# MacSet-L-V2_0_0_2.net
KiCad netlist of a schematic drawn in Altium Designer
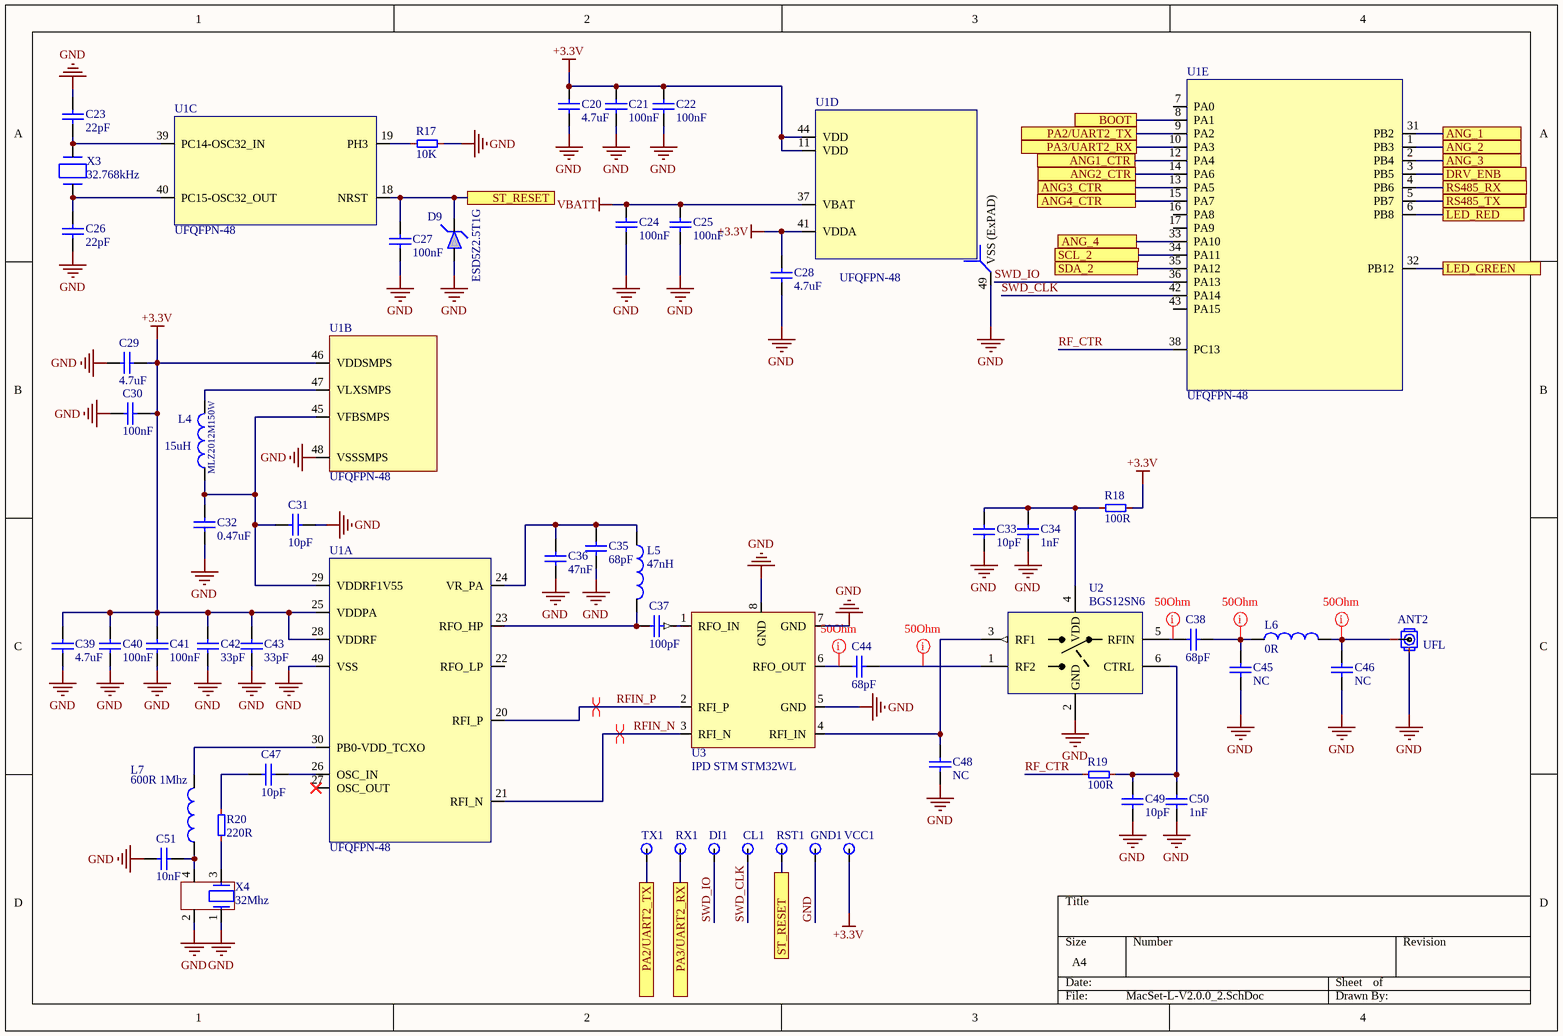
[diagram p0: MacSet-L-V2.0.0_2.SchDoc]

(export (version "E")
  (design (tool "Eeschema 10.0.6"))
  (components
    (comp (ref "ANT2")
      (value "UFL")
      (footprint "UFL")
      (description "SMA Connector")
      (libsource (lib "macnman_3.0") (part "SMA Antenna"))
    )
    (comp (ref "C20")
      (value "4.7uF")
      (footprint "CAP0603")
      (description "MLCC - SMD/SMT 4.7 uF 16 VDC 10% 0603 X5R")
      (fields
        (field (name "MANUFACTURER_PART_NUMBER") "CL10A475KQ8NNNC")
        (field (name "MANUFACTURER") "Samsung Electro-Mechanics")
      )
      (libsource (lib "macnman_2.0") (part "Capa_0603"))
    )
    (comp (ref "C21")
      (value "100nF")
      (footprint "CAP0402")
      (description "Ceramic Capacitor X7R 0402 100nF 16V")
      (fields
        (field (name "MANUFACTURER_PART_NUMBER") "GRM155R71C104JA88D")
        (field (name "MANUFACTURER") "MURATA")
      )
      (libsource (lib "macnman_2.0") (part "Capa_0402"))
    )
    (comp (ref "C22")
      (value "100nF")
      (footprint "CAP0402")
      (description "Ceramic Capacitor X7R 0402 100nF 16V")
      (fields
        (field (name "MANUFACTURER_PART_NUMBER") "GRM155R71C104JA88D")
        (field (name "MANUFACTURER") "MURATA")
      )
      (libsource (lib "macnman_2.0") (part "Capa_0402"))
    )
    (comp (ref "C23")
      (value "22pF")
      (footprint "CAP0402")
      (description "Multilayer Ceramic Capacitors MLCC - SMD/SMT 50 V 22pF C0G 0402 5%")
      (fields
        (field (name "MANUFACTURER_PART_NUMBER") "GCM1555C1H220JA16D")
        (field (name "MANUFACTURER") "Murata")
      )
      (libsource (lib "macnman_2.0") (part "Capa_0402"))
    )
    (comp (ref "C24")
      (value "100nF")
      (footprint "CAP0402")
      (description "Ceramic Capacitor X7R 0402 100nF 16V")
      (fields
        (field (name "MANUFACTURER_PART_NUMBER") "GRM155R71C104JA88D")
        (field (name "MANUFACTURER") "MURATA")
      )
      (libsource (lib "macnman_2.0") (part "Capa_0402"))
    )
    (comp (ref "C25")
      (value "100nF")
      (footprint "CAP0402")
      (description "Ceramic Capacitor X7R 0402 100nF 16V")
      (fields
        (field (name "MANUFACTURER_PART_NUMBER") "GRM155R71C104JA88D")
        (field (name "MANUFACTURER") "MURATA")
      )
      (libsource (lib "macnman_2.0") (part "Capa_0402"))
    )
    (comp (ref "C26")
      (value "22pF")
      (footprint "CAP0402")
      (description "Multilayer Ceramic Capacitors MLCC - SMD/SMT 50 V 22pF C0G 0402 5%")
      (fields
        (field (name "MANUFACTURER_PART_NUMBER") "GCM1555C1H220JA16D")
        (field (name "MANUFACTURER") "Murata")
      )
      (libsource (lib "macnman_2.0") (part "Capa_0402"))
    )
    (comp (ref "C27")
      (value "100nF")
      (footprint "CAP0402")
      (description "Ceramic Capacitor X7R 0402 100nF 16V")
      (fields
        (field (name "MANUFACTURER_PART_NUMBER") "GRM155R71C104JA88D")
        (field (name "MANUFACTURER") "MURATA")
      )
      (libsource (lib "macnman_2.0") (part "Capa_0402"))
    )
    (comp (ref "C28")
      (value "4.7uF")
      (footprint "CAP0603")
      (description "MLCC - SMD/SMT 4.7 uF 16 VDC 10% 0603 X5R")
      (fields
        (field (name "MANUFACTURER_PART_NUMBER") "CL10A475KQ8NNNC")
        (field (name "MANUFACTURER") "Samsung Electro-Mechanics")
      )
      (libsource (lib "macnman_2.0") (part "Capa_0603"))
    )
    (comp (ref "C29")
      (value "4.7uF")
      (footprint "CAP0603")
      (description "MLCC - SMD/SMT 4.7 uF 16 VDC 10% 0603 X5R")
      (fields
        (field (name "MANUFACTURER_PART_NUMBER") "CL10A475KQ8NNNC")
        (field (name "MANUFACTURER") "Samsung Electro-Mechanics")
      )
      (libsource (lib "macnman_2.0") (part "Capa_0603"))
    )
    (comp (ref "C30")
      (value "100nF")
      (footprint "CAP0402")
      (description "Ceramic Capacitor X7R 0402 100nF 16V")
      (fields
        (field (name "MANUFACTURER_PART_NUMBER") "GRM155R71C104JA88D")
        (field (name "MANUFACTURER") "MURATA")
      )
      (libsource (lib "macnman_2.0") (part "Capa_0402"))
    )
    (comp (ref "C31")
      (value "10pF")
      (footprint "CAP0402")
      (description "Multilayer Ceramic Capacitors MLCC - SMD/SMT 50 V 10pF C0G 0402 10%")
      (fields
        (field (name "MANUFACTURER_PART_NUMBER") "CC0402JRNPO9BN100")
        (field (name "MANUFACTURER") "YAGEO")
      )
      (libsource (lib "macnman_2.0") (part "Capa_0402"))
    )
    (comp (ref "C32")
      (value "0.47uF")
      (footprint "CAP0603")
      (description "MLCC - SMD/SMT 0.47 uF 16 VDC 10% 0603 X5R")
      (fields
        (field (name "MANUFACTURER_PART_NUMBER") "CC0603KRX7R0BB474")
        (field (name "MANUFACTURER") "Yageo")
      )
      (libsource (lib "macnman_2.0") (part "Capa_0603"))
    )
    (comp (ref "C33")
      (value "10pF")
      (footprint "CAP0402")
      (description "Multilayer Ceramic Capacitors MLCC - SMD/SMT 50 V 10pF C0G 0402 10%")
      (fields
        (field (name "MANUFACTURER_PART_NUMBER") "CC0402JRNPO9BN100")
        (field (name "MANUFACTURER") "YAGEO")
      )
      (libsource (lib "macnman_2.0") (part "Capa_0402"))
    )
    (comp (ref "C34")
      (value "1nF")
      (footprint "CAP0402")
      (description "Multilayer Ceramic Capacitors MLCC - SMD/SMT 50 V 1nF C0G 0402 10%")
      (fields
        (field (name "MANUFACTURER_PART_NUMBER") "CC0402KRX7R9BB102")
        (field (name "MANUFACTURER") "YAGEO")
      )
      (libsource (lib "macnman_2.0") (part "Capa_0402"))
    )
    (comp (ref "C35")
      (value "68pF")
      (footprint "CAP0402")
      (description "Multilayer Ceramic Capacitors MLCC - SMD/SMT 50 V 68pF C0G 0402 5%")
      (fields
        (field (name "MANUFACTURER_PART_NUMBER") "CC0402JRNPO9BN680")
        (field (name "MANUFACTURER") "YAGEO")
      )
      (libsource (lib "macnman_2.0") (part "Capa_0402"))
    )
    (comp (ref "C36")
      (value "47nF")
      (footprint "CAP0402")
      (description "Multilayer Ceramic Capacitors MLCC - SMD/SMT 50 V 47nF C0G 0402 10%")
      (fields
        (field (name "MANUFACTURER_PART_NUMBER") "0402B473K500CT")
        (field (name "MANUFACTURER") "Walsin")
      )
      (libsource (lib "macnman_2.0") (part "Capa_0402"))
    )
    (comp (ref "C37")
      (value "100pF")
      (footprint "CAP0402")
      (description "Multilayer Ceramic Capacitors MLCC - SMD/SMT 50 V 100pF C0G 0402 10%")
      (fields
        (field (name "MANUFACTURER_PART_NUMBER") "CC0402KRNPO9BN101")
        (field (name "MANUFACTURER") "YAGEO")
      )
      (libsource (lib "") (part "Capa_0402_1"))
    )
    (comp (ref "C38")
      (value "68pF")
      (footprint "CAP0402")
      (description "Multilayer Ceramic Capacitors MLCC - SMD/SMT 50 V 68pF C0G 0402 5%")
      (fields
        (field (name "MANUFACTURER_PART_NUMBER") "CC0402JRNPO9BN680")
        (field (name "MANUFACTURER") "YAGEO")
      )
      (libsource (lib "macnman_2.0") (part "Capa_0402"))
    )
    (comp (ref "C39")
      (value "4.7uF")
      (footprint "CAP0603")
      (description "MLCC - SMD/SMT 4.7 uF 16 VDC 10% 0603 X5R")
      (fields
        (field (name "MANUFACTURER_PART_NUMBER") "CL10A475KQ8NNNC")
        (field (name "MANUFACTURER") "Samsung Electro-Mechanics")
      )
      (libsource (lib "macnman_2.0") (part "Capa_0603"))
    )
    (comp (ref "C40")
      (value "100nF")
      (footprint "CAP0402")
      (description "Ceramic Capacitor X7R 0402 100nF 16V")
      (fields
        (field (name "MANUFACTURER_PART_NUMBER") "GRM155R71C104JA88D")
        (field (name "MANUFACTURER") "MURATA")
      )
      (libsource (lib "macnman_2.0") (part "Capa_0402"))
    )
    (comp (ref "C41")
      (value "100nF")
      (footprint "CAP0402")
      (description "Ceramic Capacitor X7R 0402 100nF 16V")
      (fields
        (field (name "MANUFACTURER_PART_NUMBER") "GRM155R71C104JA88D")
        (field (name "MANUFACTURER") "MURATA")
      )
      (libsource (lib "macnman_2.0") (part "Capa_0402"))
    )
    (comp (ref "C42")
      (value "33pF")
      (footprint "CAP0402")
      (description "Ceramic Capacitor C0G, NP0 0402 33pF 35V")
      (fields
        (field (name "MANUFACTURER_PART_NUMBER") "CC0402JRNPO9BN330")
        (field (name "MANUFACTURER") "MURATA")
      )
      (libsource (lib "macnman_2.0") (part "Capa_0402"))
    )
    (comp (ref "C43")
      (value "33pF")
      (footprint "CAP0402")
      (description "Ceramic Capacitor C0G, NP0 0402 33pF 35V")
      (fields
        (field (name "MANUFACTURER_PART_NUMBER") "CC0402JRNPO9BN330")
        (field (name "MANUFACTURER") "MURATA")
      )
      (libsource (lib "macnman_2.0") (part "Capa_0402"))
    )
    (comp (ref "C44")
      (value "68pF")
      (footprint "CAP0402")
      (description "Multilayer Ceramic Capacitors MLCC - SMD/SMT 50 V 68pF C0G 0402 5%")
      (fields
        (field (name "MANUFACTURER_PART_NUMBER") "CC0402JRNPO9BN680")
        (field (name "MANUFACTURER") "YAGEO")
      )
      (libsource (lib "macnman_2.0") (part "Capa_0402"))
    )
    (comp (ref "C45")
      (value "NC")
      (footprint "CAP0402")
      (description "Multilayer Ceramic Capacitors MLCC - SMD/SMT 50 V 2.4pF C0G 0402 10%")
      (fields
        (field (name "MANUFACTURER_PART_NUMBER") "CC0402CRNPO9BN2R4")
        (field (name "MANUFACTURER") "YAGEO")
      )
      (libsource (lib "macnman_2.0") (part "Capa_0402"))
    )
    (comp (ref "C46")
      (value "NC")
      (footprint "CAP0402")
      (description "Multilayer Ceramic Capacitors MLCC - SMD/SMT 50 V 2.4pF C0G 0402 10%")
      (fields
        (field (name "MANUFACTURER_PART_NUMBER") "CC0402CRNPO9BN2R4")
        (field (name "MANUFACTURER") "YAGEO")
      )
      (libsource (lib "macnman_2.0") (part "Capa_0402"))
    )
    (comp (ref "C47")
      (value "10pF")
      (footprint "CAP0402")
      (description "Multilayer Ceramic Capacitors MLCC - SMD/SMT 50 V 10pF C0G 0402 10%")
      (fields
        (field (name "MANUFACTURER_PART_NUMBER") "CC0402JRNPO9BN100")
        (field (name "MANUFACTURER") "YAGEO")
      )
      (libsource (lib "macnman_2.0") (part "Capa_0402"))
    )
    (comp (ref "C48") (value "NC") (footprint "CAP0402") (libsource (lib "macnman_2.0") (part "Capa_0402")))
    (comp (ref "C49")
      (value "10pF")
      (footprint "CAP0402")
      (description "Multilayer Ceramic Capacitors MLCC - SMD/SMT 50 V 10pF C0G 0402 10%")
      (fields
        (field (name "MANUFACTURER_PART_NUMBER") "CC0402JRNPO9BN100")
        (field (name "MANUFACTURER") "YAGEO")
      )
      (libsource (lib "macnman_2.0") (part "Capa_0402"))
    )
    (comp (ref "C50")
      (value "1nF")
      (footprint "CAP0402")
      (description "Multilayer Ceramic Capacitors MLCC - SMD/SMT 50 V 1nF C0G 0402 10%")
      (fields
        (field (name "MANUFACTURER_PART_NUMBER") "CC0402KRX7R9BB102")
        (field (name "MANUFACTURER") "YAGEO")
      )
      (libsource (lib "macnman_2.0") (part "Capa_0402"))
    )
    (comp (ref "C51")
      (value "10nF")
      (footprint "CAP0402")
      (description "Multilayer Ceramic Capacitors MLCC - SMD/SMT 50 V 10nF C0G 0402 10%")
      (fields
        (field (name "MANUFACTURER_PART_NUMBER") "CC0402KRX7R9BB103")
        (field (name "MANUFACTURER") "YAGEO")
      )
      (libsource (lib "macnman_2.0") (part "Capa_0402"))
    )
    (comp (ref "CL1")
      (value "-")
      (footprint "TH_Pad")
      (description "Through Hole pad 1mm 0.5mm Hole")
      (libsource (lib "macnman_2.0") (part "TH_PAD"))
    )
    (comp (ref "D9")
      (value "ESD5Z2.5T1G")
      (footprint "SOD523")
      (description "ESD Protection Diodes / TVS Diodes 2.5V ESD Protection Unidirectional")
      (fields (field (name "MANUFACTURER") "onsemi"))
      (libsource (lib "macnman_2.0") (part "DIODE-ESD"))
    )
    (comp (ref "DI1")
      (value "-")
      (footprint "TH_Pad")
      (description "Through Hole pad 1mm 0.5mm Hole")
      (libsource (lib "macnman_2.0") (part "TH_PAD"))
    )
    (comp (ref "GND1")
      (value "-")
      (footprint "TH_Pad")
      (description "Through Hole pad 1mm 0.5mm Hole")
      (libsource (lib "macnman_2.0") (part "TH_PAD"))
    )
    (comp (ref "L4")
      (value "15uH")
      (footprint "IND_2012")
      (description "MLZ2012 Multilayer Shielded Inductor 15µH, ±5%")
      (fields (field (name "MANUFACTURER_PART_NUMBER") "MLZ2012M150W") (field (name "MANUFACTURER") "TDK"))
      (libsource (lib "MB1849") (part "Inductor"))
    )
    (comp (ref "L5")
      (value "47nH")
      (footprint "IND_0402")
      (description "47nH High frequency chip inductor ±5%  0402")
      (fields
        (field (name "MANUFACTURER_PART_NUMBER") "LQG15HN47NJ02D")
        (field (name "MANUFACTURER") "Murata")
      )
      (libsource (lib "macnman_2.0") (part "Inductor"))
    )
    (comp (ref "L6")
      (value "0R")
      (footprint "IND_0402")
      (description "Thick Film Resistors - SMD 1/16watt 0R 1% 0402 Commercial Use")
      (fields
        (field (name "MANUFACTURER_PART_NUMBER") "RC0402FR-070RL")
        (field (name "MANUFACTURER") "YAGIO")
      )
      (libsource (lib "macnman_2.0") (part "Inductor"))
    )
    (comp (ref "L7")
      (value "600R 1Mhz")
      (footprint "IND_0402")
      (description "47nH High frequency chip inductor ±5%  0402")
      (fields (field (name "MANUFACTURER_PART_NUMBER") "GZ1005D601TF") (field (name "MANUFACTURER") "Murata"))
      (libsource (lib "macnman_2.0") (part "Inductor"))
    )
    (comp (ref "R17")
      (value "10K")
      (footprint "RESC0402")
      (description "Thick Film Resistors - SMD 1/16watt 10Kohms 0402 1% Commercial Use")
      (fields
        (field (name "MANUFACTURER_PART_NUMBER") "CRCW040210K0FKEDC")
        (field (name "MANUFACTURER") "Vishay")
      )
      (libsource (lib "macnman_2.0") (part "RES_0402"))
    )
    (comp (ref "R18")
      (value "100R")
      (footprint "RESC0402")
      (description "Thin Film Resistors 100 OHM 1% 50PPM 1/1 6W 0402")
      (fields
        (field (name "MANUFACTURER_PART_NUMBER") "RC0402FR-07100RL")
        (field (name "MANUFACTURER") "YAGEO")
      )
      (libsource (lib "macnman_2.0") (part "RES_0402"))
    )
    (comp (ref "R19")
      (value "100R")
      (footprint "RESC0402")
      (description "Thin Film Resistors 100 OHM 1% 50PPM 1/1 6W 0402")
      (fields
        (field (name "MANUFACTURER_PART_NUMBER") "RC0402FR-07100RL")
        (field (name "MANUFACTURER") "YAGEO")
      )
      (libsource (lib "macnman_2.0") (part "RES_0402"))
    )
    (comp (ref "R20")
      (value "220R")
      (footprint "RESC0402")
      (description "Thin Film Resistors 220 OHM 1% 50PPM 1/1 6W 0402")
      (fields
        (field (name "MANUFACTURER_PART_NUMBER") "0402WGF2200TCE")
        (field (name "MANUFACTURER") "Royalohm")
      )
      (libsource (lib "macnman_2.0") (part "RES_0402"))
    )
    (comp (ref "RST1")
      (value "-")
      (footprint "TH_Pad")
      (description "Through Hole pad 1mm 0.5mm Hole")
      (libsource (lib "macnman_2.0") (part "TH_PAD"))
    )
    (comp (ref "RX1")
      (value "-")
      (footprint "TH_Pad")
      (description "Through Hole pad 1mm 0.5mm Hole")
      (libsource (lib "macnman_2.0") (part "TH_PAD"))
    )
    (comp (ref "TX1")
      (value "-")
      (footprint "TH_Pad")
      (description "Through Hole pad 1mm 0.5mm Hole")
      (libsource (lib "macnman_2.0") (part "TH_PAD"))
    )
    (comp (ref "U1")
      (value "UFQFPN-48")
      (footprint "STM32WLxx_QFN48")
      (fields
        (field (name "MANUFACTURER") "STMicroelectronics")
        (field (name "MANUFACTURER_PART_NUMBER") "STM32WL5CCU6")
      )
      (libsource (lib "macnman_3.0") (part "STM32WLE5C8U6_O"))
    )
    (comp (ref "U2")
      (value "BGS12SN6")
      (footprint "SON40P70X40-6N")
      (description "DC switch - Ultra-Low  SPDT analog switch")
      (fields (field (name "MANUFACTURER") "INFINEON"))
      (libsource (lib "macnman_2.0") (part "BGS12SN6"))
    )
    (comp (ref "U3")
      (value "IPD STM STM32WL")
      (footprint "IPD STM")
      (fields
        (field (name "MANUFACTURER") "STMICROELECTRONICS")
        (field (name "MANUFACTURER_PART_NUMBER") "MLPF-WL-02D3")
      )
      (libsource (lib "macnman_3.0") (part "IPD ST STM32WL"))
    )
    (comp (ref "VCC1")
      (value "-")
      (footprint "TH_Pad")
      (description "Through Hole pad 1mm 0.5mm Hole")
      (libsource (lib "macnman_2.0") (part "TH_PAD"))
    )
    (comp (ref "X3")
      (value "32.768kHz")
      (footprint "OSC_3215")
      (description "Crystal Osc 3215 32.768kHz 12pF")
      (fields
        (field (name "MANUFACTURER_PART_NUMBER") "ECS-.327-12.5-34B-TR")
        (field (name "MANUFACTURER") "ECS")
      )
      (libsource (lib "macnman_2.0") (part "OSC_2012"))
    )
    (comp (ref "X4")
      (value "32Mhz")
      (footprint "OSC_2016")
      (description "TCXO Oscillators TG2016SMN 32.0000M-MCGNNM0: TCXO 2.8V 3.3V 0.5PPM -40 85C NON O/E 1K TR")
      (fields
        (field (name "MANUFACTURER_PART_NUMBER") "TG2016SMN 32.0000M-MCGNNM0")
        (field (name "MANUFACTURER") "Epson")
      )
      (libsource (lib "macnman_2.0") (part "OSC_2016"))
    )
  )
  (nets
    (net (code "1") (name "+3.3V") (class "Default")
      (node (ref "C20") (pin "2") (pinfunction "2_2") (pintype "passive"))
      (node (ref "C21") (pin "1") (pinfunction "1_1") (pintype "passive"))
      (node (ref "C22") (pin "1") (pinfunction "1_1") (pintype "passive"))
      (node (ref "C28") (pin "2") (pinfunction "2_2") (pintype "passive"))
      (node (ref "C29") (pin "2") (pinfunction "2_2") (pintype "passive"))
      (node (ref "C30") (pin "1") (pinfunction "1_1") (pintype "passive"))
      (node (ref "C39") (pin "2") (pinfunction "2_2") (pintype "passive"))
      (node (ref "C40") (pin "1") (pinfunction "1_1") (pintype "passive"))
      (node (ref "C41") (pin "1") (pinfunction "1_1") (pintype "passive"))
      (node (ref "C42") (pin "1") (pinfunction "1_1") (pintype "passive"))
      (node (ref "C43") (pin "1") (pinfunction "1_1") (pintype "passive"))
      (node (ref "R18") (pin "1") (pinfunction "1_1") (pintype "passive"))
      (node (ref "U1") (pin "11") (pinfunction "VDD_11") (pintype "passive"))
      (node (ref "U1") (pin "25") (pinfunction "VDDPA_25") (pintype "passive"))
      (node (ref "U1") (pin "28") (pinfunction "VDDRF_28") (pintype "passive"))
      (node (ref "U1") (pin "41") (pinfunction "VDDA_41") (pintype "passive"))
      (node (ref "U1") (pin "44") (pinfunction "VDD_44") (pintype "passive"))
      (node (ref "U1") (pin "46") (pinfunction "VDDSMPS_46") (pintype "passive"))
      (node (ref "VCC1") (pin "1") (pinfunction "RX_1") (pintype "passive"))
    )
    (net (code "2") (name "/ANG1_CTR") (class "Default")
      (node (ref "U1") (pin "12") (pinfunction "PA4_12") (pintype "passive"))
    )
    (net (code "3") (name "/ANG2_CTR") (class "Default")
      (node (ref "U1") (pin "14") (pinfunction "PA6_14") (pintype "passive"))
    )
    (net (code "4") (name "/ANG3_CTR") (class "Default")
      (node (ref "U1") (pin "13") (pinfunction "PA5_13") (pintype "passive"))
    )
    (net (code "5") (name "/ANG4_CTR") (class "Default")
      (node (ref "U1") (pin "15") (pinfunction "PA7_15") (pintype "passive"))
    )
    (net (code "6") (name "/ANG_1") (class "Default")
      (node (ref "U1") (pin "31") (pinfunction "PB2_31") (pintype "passive"))
    )
    (net (code "7") (name "/ANG_2") (class "Default")
      (node (ref "U1") (pin "1") (pinfunction "PB3_1") (pintype "passive"))
    )
    (net (code "8") (name "/ANG_3") (class "Default")
      (node (ref "U1") (pin "2") (pinfunction "PB4_2") (pintype "passive"))
    )
    (net (code "9") (name "/ANG_4") (class "Default")
      (node (ref "U1") (pin "33") (pinfunction "PA10_33") (pintype "passive"))
    )
    (net (code "10") (name "/BOOT") (class "Default")
      (node (ref "U1") (pin "8") (pinfunction "PA1_8") (pintype "passive"))
    )
    (net (code "11") (name "/DRV_ENB") (class "Default")
      (node (ref "U1") (pin "3") (pinfunction "PB5_3") (pintype "passive"))
    )
    (net (code "12") (name "/LED_GREEN") (class "Default")
      (node (ref "U1") (pin "32") (pinfunction "PB12_32") (pintype "passive"))
    )
    (net (code "13") (name "/LED_RED") (class "Default")
      (node (ref "U1") (pin "6") (pinfunction "PB8_6") (pintype "passive"))
    )
    (net (code "14") (name "/PA2{slash}UART2_TX") (class "Default")
      (node (ref "TX1") (pin "1") (pinfunction "RX_1") (pintype "passive"))
      (node (ref "U1") (pin "9") (pinfunction "PA2_9") (pintype "passive"))
    )
    (net (code "15") (name "/PA3{slash}UART2_RX") (class "Default")
      (node (ref "RX1") (pin "1") (pinfunction "RX_1") (pintype "passive"))
      (node (ref "U1") (pin "10") (pinfunction "PA3_10") (pintype "passive"))
    )
    (net (code "16") (name "/RFIN_N") (class "Default")
      (node (ref "U1") (pin "21") (pinfunction "RFI_N_21") (pintype "passive"))
      (node (ref "U3") (pin "3") (pinfunction "RFI_N_3") (pintype "output"))
    )
    (net (code "17") (name "/RFIN_P") (class "Default")
      (node (ref "U1") (pin "20") (pinfunction "RFI_P_20") (pintype "passive"))
      (node (ref "U3") (pin "2") (pinfunction "RFI_P_2") (pintype "output"))
    )
    (net (code "18") (name "/RF_CTR") (class "Default")
      (node (ref "R19") (pin "1") (pinfunction "1_1") (pintype "passive"))
      (node (ref "U1") (pin "38") (pinfunction "PC13_38") (pintype "passive"))
    )
    (net (code "19") (name "/RS485_RX") (class "Default")
      (node (ref "U1") (pin "4") (pinfunction "PB6_4") (pintype "passive"))
    )
    (net (code "20") (name "/RS485_TX") (class "Default")
      (node (ref "U1") (pin "5") (pinfunction "PB7_5") (pintype "passive"))
    )
    (net (code "21") (name "/SCL_2") (class "Default")
      (node (ref "U1") (pin "34") (pinfunction "PA11_34") (pintype "passive"))
    )
    (net (code "22") (name "/SDA_2") (class "Default")
      (node (ref "U1") (pin "35") (pinfunction "PA12_35") (pintype "passive"))
    )
    (net (code "23") (name "/ST_RESET") (class "Default")
      (node (ref "C27") (pin "1") (pinfunction "1_1") (pintype "passive"))
      (node (ref "D9") (pin "1") (pinfunction "K_1") (pintype "passive"))
      (node (ref "RST1") (pin "1") (pinfunction "RX_1") (pintype "passive"))
      (node (ref "U1") (pin "18") (pinfunction "NRST_18") (pintype "passive"))
    )
    (net (code "24") (name "/SWD_CLK") (class "Default")
      (node (ref "CL1") (pin "1") (pinfunction "RX_1") (pintype "passive"))
      (node (ref "U1") (pin "42") (pinfunction "PA14_42") (pintype "passive"))
    )
    (net (code "25") (name "/SWD_IO") (class "Default")
      (node (ref "DI1") (pin "1") (pinfunction "RX_1") (pintype "passive"))
      (node (ref "U1") (pin "36") (pinfunction "PA13_36") (pintype "passive"))
    )
    (net (code "26") (name "GND") (class "Default")
      (node (ref "ANT2") (pin "2") (pinfunction "Value_2") (pintype "passive"))
      (node (ref "C20") (pin "1") (pinfunction "1_1") (pintype "passive"))
      (node (ref "C21") (pin "2") (pinfunction "2_2") (pintype "passive"))
      (node (ref "C22") (pin "2") (pinfunction "2_2") (pintype "passive"))
      (node (ref "C23") (pin "2") (pinfunction "2_2") (pintype "passive"))
      (node (ref "C24") (pin "2") (pinfunction "2_2") (pintype "passive"))
      (node (ref "C25") (pin "2") (pinfunction "2_2") (pintype "passive"))
      (node (ref "C26") (pin "1") (pinfunction "1_1") (pintype "passive"))
      (node (ref "C27") (pin "2") (pinfunction "2_2") (pintype "passive"))
      (node (ref "C28") (pin "1") (pinfunction "1_1") (pintype "passive"))
      (node (ref "C29") (pin "1") (pinfunction "1_1") (pintype "passive"))
      (node (ref "C30") (pin "2") (pinfunction "2_2") (pintype "passive"))
      (node (ref "C31") (pin "1") (pinfunction "1_1") (pintype "passive"))
      (node (ref "C32") (pin "1") (pinfunction "1_1") (pintype "passive"))
      (node (ref "C33") (pin "1") (pinfunction "1_1") (pintype "passive"))
      (node (ref "C34") (pin "1") (pinfunction "1_1") (pintype "passive"))
      (node (ref "C35") (pin "1") (pinfunction "1_1") (pintype "passive"))
      (node (ref "C36") (pin "1") (pinfunction "1_1") (pintype "passive"))
      (node (ref "C39") (pin "1") (pinfunction "1_1") (pintype "passive"))
      (node (ref "C40") (pin "2") (pinfunction "2_2") (pintype "passive"))
      (node (ref "C41") (pin "2") (pinfunction "2_2") (pintype "passive"))
      (node (ref "C42") (pin "2") (pinfunction "2_2") (pintype "passive"))
      (node (ref "C43") (pin "2") (pinfunction "2_2") (pintype "passive"))
      (node (ref "C45") (pin "1") (pinfunction "1_1") (pintype "passive"))
      (node (ref "C46") (pin "1") (pinfunction "1_1") (pintype "passive"))
      (node (ref "C48") (pin "2") (pinfunction "2_2") (pintype "passive"))
      (node (ref "C49") (pin "1") (pinfunction "1_1") (pintype "passive"))
      (node (ref "C50") (pin "1") (pinfunction "1_1") (pintype "passive"))
      (node (ref "C51") (pin "2") (pinfunction "2_2") (pintype "passive"))
      (node (ref "D9") (pin "2") (pinfunction "A_2") (pintype "passive"))
      (node (ref "GND1") (pin "1") (pinfunction "RX_1") (pintype "passive"))
      (node (ref "R17") (pin "1") (pinfunction "1_1") (pintype "passive"))
      (node (ref "U1") (pin "48") (pinfunction "VSSSMPS_48") (pintype "passive"))
      (node (ref "U1") (pin "49") (pinfunction "VSS_(ExPAD)_49") (pintype "passive"))
      (node (ref "U2") (pin "2") (pinfunction "GND_2") (pintype "passive"))
      (node (ref "U3") (pin "5") (pinfunction "GND_5") (pintype "power_in"))
      (node (ref "U3") (pin "7") (pinfunction "GND_7") (pintype "power_in"))
      (node (ref "U3") (pin "8") (pinfunction "GND_8") (pintype "power_in"))
      (node (ref "X4") (pin "1") (pinfunction "1_1") (pintype "passive"))
      (node (ref "X4") (pin "2") (pinfunction "2_2") (pintype "passive"))
    )
    (net (code "27") (name "Net-(ANT2-Value-Pad1)") (class "Default")
      (node (ref "ANT2") (pin "1") (pinfunction "Value_1") (pintype "passive"))
      (node (ref "C46") (pin "2") (pinfunction "2_2") (pintype "passive"))
      (node (ref "L6") (pin "2") (pintype "passive"))
    )
    (net (code "28") (name "Net-(C38-Pad1)") (class "Default")
      (node (ref "C38") (pin "1") (pinfunction "1_1") (pintype "passive"))
      (node (ref "C45") (pin "2") (pinfunction "2_2") (pintype "passive"))
      (node (ref "L6") (pin "1") (pintype "passive"))
    )
    (net (code "29") (name "Net-(C47-Pad1)") (class "Default")
      (node (ref "C47") (pin "1") (pinfunction "1_1") (pintype "passive"))
      (node (ref "R20") (pin "2") (pinfunction "2_2") (pintype "passive"))
    )
    (net (code "30") (name "Net-(C51-Pad1)") (class "Default")
      (node (ref "C51") (pin "1") (pinfunction "1_1") (pintype "passive"))
      (node (ref "L7") (pin "1") (pintype "passive"))
      (node (ref "X4") (pin "4") (pinfunction "4_4") (pintype "passive"))
    )
    (net (code "31") (name "Net-(R20-Pad1)") (class "Default")
      (node (ref "R20") (pin "1") (pinfunction "1_1") (pintype "passive"))
      (node (ref "X4") (pin "3") (pinfunction "3_3") (pintype "passive"))
    )
    (net (code "32") (name "Net-(U1A-OSC_IN)") (class "Default")
      (node (ref "C47") (pin "2") (pinfunction "2_2") (pintype "passive"))
      (node (ref "U1") (pin "26") (pinfunction "OSC_IN_26") (pintype "passive"))
    )
    (net (code "33") (name "Net-(U1A-PB0-VDD_TCXO)") (class "Default")
      (node (ref "L7") (pin "2") (pintype "passive"))
      (node (ref "U1") (pin "30") (pinfunction "PB0-VDD_TCXO_30") (pintype "passive"))
    )
    (net (code "34") (name "Net-(U1A-RFO_HP)") (class "Default")
      (node (ref "C37") (pin "2") (pinfunction "2_2") (pintype "passive"))
      (node (ref "L5") (pin "2") (pintype "passive"))
      (node (ref "U1") (pin "23") (pinfunction "RFO_HP_23") (pintype "passive"))
    )
    (net (code "35") (name "Net-(U1A-VDDRF1V55)") (class "Default")
      (node (ref "C31") (pin "2") (pinfunction "2_2") (pintype "passive"))
      (node (ref "C32") (pin "2") (pinfunction "2_2") (pintype "passive"))
      (node (ref "L4") (pin "1") (pinfunction "1_1") (pintype "passive"))
      (node (ref "U1") (pin "29") (pinfunction "VDDRF1V55_29") (pintype "passive"))
      (node (ref "U1") (pin "45") (pinfunction "VFBSMPS_45") (pintype "passive"))
    )
    (net (code "36") (name "Net-(U1A-VR_PA)") (class "Default")
      (node (ref "C35") (pin "2") (pinfunction "2_2") (pintype "passive"))
      (node (ref "C36") (pin "2") (pinfunction "2_2") (pintype "passive"))
      (node (ref "L5") (pin "1") (pintype "passive"))
      (node (ref "U1") (pin "24") (pinfunction "VR_PA_24") (pintype "passive"))
    )
    (net (code "37") (name "Net-(U1B-VLXSMPS)") (class "Default")
      (node (ref "L4") (pin "2") (pinfunction "2_2") (pintype "passive"))
      (node (ref "U1") (pin "47") (pinfunction "VLXSMPS_47") (pintype "passive"))
    )
    (net (code "38") (name "Net-(U1C-PC14-OSC32_IN)") (class "Default")
      (node (ref "C23") (pin "1") (pinfunction "1_1") (pintype "passive"))
      (node (ref "U1") (pin "39") (pinfunction "PC14-OSC32_IN_39") (pintype "passive"))
      (node (ref "X3") (pin "2") (pinfunction "X2_2") (pintype "passive"))
    )
    (net (code "39") (name "Net-(U1C-PC15-OSC32_OUT)") (class "Default")
      (node (ref "C26") (pin "2") (pinfunction "2_2") (pintype "passive"))
      (node (ref "U1") (pin "40") (pinfunction "PC15-OSC32_OUT_40") (pintype "passive"))
      (node (ref "X3") (pin "1") (pinfunction "X1_1") (pintype "passive"))
    )
    (net (code "40") (name "Net-(U1C-PH3)") (class "Default")
      (node (ref "R17") (pin "2") (pinfunction "2_2") (pintype "passive"))
      (node (ref "U1") (pin "19") (pinfunction "PH3_19") (pintype "passive"))
    )
    (net (code "41") (name "Net-(U2-CTRL)") (class "Default")
      (node (ref "C49") (pin "2") (pinfunction "2_2") (pintype "passive"))
      (node (ref "C50") (pin "2") (pinfunction "2_2") (pintype "passive"))
      (node (ref "R19") (pin "2") (pinfunction "2_2") (pintype "passive"))
      (node (ref "U2") (pin "6") (pinfunction "CTRL_6") (pintype "passive"))
    )
    (net (code "42") (name "Net-(U2-RF1)") (class "Default")
      (node (ref "C48") (pin "1") (pinfunction "1_1") (pintype "passive"))
      (node (ref "U2") (pin "3") (pinfunction "RF1_3") (pintype "output"))
      (node (ref "U3") (pin "4") (pinfunction "RFI_IN_4") (pintype "input"))
    )
    (net (code "43") (name "Net-(U2-RF2)") (class "Default")
      (node (ref "C44") (pin "1") (pinfunction "1_1") (pintype "passive"))
      (node (ref "U2") (pin "1") (pinfunction "RF2_1") (pintype "passive"))
    )
    (net (code "44") (name "Net-(U2-RFIN)") (class "Default")
      (node (ref "C38") (pin "2") (pinfunction "2_2") (pintype "passive"))
      (node (ref "U2") (pin "5") (pinfunction "RFIN_5") (pintype "passive"))
    )
    (net (code "45") (name "Net-(U2-VDD)") (class "Default")
      (node (ref "C33") (pin "2") (pinfunction "2_2") (pintype "passive"))
      (node (ref "C34") (pin "2") (pinfunction "2_2") (pintype "passive"))
      (node (ref "R18") (pin "2") (pinfunction "2_2") (pintype "passive"))
      (node (ref "U2") (pin "4") (pinfunction "VDD_4") (pintype "passive"))
    )
    (net (code "46") (name "Net-(U3-RFO_IN)") (class "Default")
      (node (ref "C37") (pin "1") (pinfunction "1_1") (pintype "output"))
      (node (ref "U3") (pin "1") (pinfunction "RFO_IN_1") (pintype "input"))
    )
    (net (code "47") (name "Net-(U3-RFO_OUT)") (class "Default")
      (node (ref "C44") (pin "2") (pinfunction "2_2") (pintype "passive"))
      (node (ref "U3") (pin "6") (pinfunction "RFO_OUT_6") (pintype "output"))
    )
    (net (code "48") (name "VBATT") (class "Default")
      (node (ref "C24") (pin "1") (pinfunction "1_1") (pintype "passive"))
      (node (ref "C25") (pin "1") (pinfunction "1_1") (pintype "passive"))
      (node (ref "U1") (pin "37") (pinfunction "VBAT_37") (pintype "passive"))
    )
    (net (code "49") (name "unconnected-(U1A-OSC_OUT-Pad27)") (class "Default")
      (node (ref "U1") (pin "27") (pinfunction "OSC_OUT_27") (pintype "passive+no_connect"))
    )
    (net (code "50") (name "unconnected-(U1A-RFO_LP-Pad22)") (class "Default")
      (node (ref "U1") (pin "22") (pinfunction "RFO_LP_22") (pintype "passive"))
    )
    (net (code "51") (name "unconnected-(U1E-PA0-Pad7)") (class "Default")
      (node (ref "U1") (pin "7") (pinfunction "PA0_7") (pintype "passive"))
    )
    (net (code "52") (name "unconnected-(U1E-PA8-Pad16)") (class "Default")
      (node (ref "U1") (pin "16") (pinfunction "PA8_16") (pintype "passive"))
    )
    (net (code "53") (name "unconnected-(U1E-PA9-Pad17)") (class "Default")
      (node (ref "U1") (pin "17") (pinfunction "PA9_17") (pintype "passive"))
    )
    (net (code "54") (name "unconnected-(U1E-PA15-Pad43)") (class "Default")
      (node (ref "U1") (pin "43") (pinfunction "PA15_43") (pintype "passive"))
    )
  )
)
